# controller.net
KiCad netlist of a schematic drawn in EAGLE
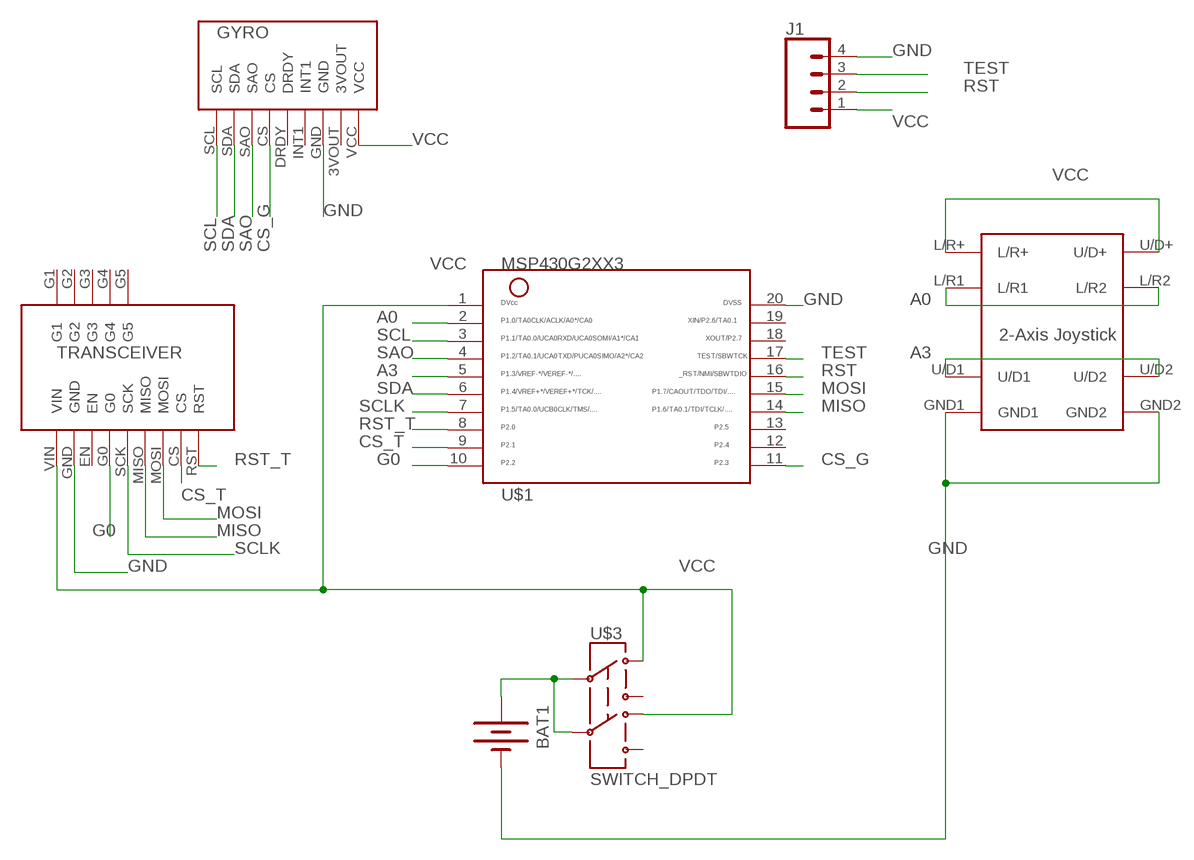
[diagram p0: schematic, sheet 1]

(export (version "E")
  (design (tool "Eeschema 10.0.6"))
  (components
    (comp (ref "BAT1")
      (value "BATTERY")
      (footprint "eagle-import:BATTERY_PACK_2AA")
      (libsource (lib "eagle-import") (part "BATTERY"))
    )
    (comp (ref "J1")
      (value "CONN_04LOCK")
      (footprint "eagle-import:1X04_LOCK")
      (libsource (lib "eagle-import") (part "CONN_04LOCK"))
    )
    (comp (ref "U$1")
      (value "MSP430G2XX3TSSOP")
      (footprint "eagle-import:PW20")
      (libsource (lib "eagle-import") (part "MSP430G2XX3TSSOP"))
    )
    (comp (ref "U$2")
      (value "PARALLAX-2AXIS-JOYSTICK")
      (footprint "eagle-import:PARALLAX-2AXIS-JOYSTICK")
      (libsource (lib "eagle-import") (part "PARALLAX-2AXIS-JOYSTICK"))
    )
    (comp (ref "U$3")
      (value "SWITCH_DPDT")
      (footprint "eagle-import:JS_DPDT_TH")
      (libsource (lib "eagle-import") (part "SWITCH_DPDT"))
    )
    (comp (ref "U$4")
      (value "ADAFRUIT-RFM69HCW-TRANSCEIVER")
      (footprint "eagle-import:ADAFRUIT-RFM69HCW-TRANSCEIVER")
      (libsource (lib "eagle-import") (part "ADAFRUIT-RFM69HCW-TRANSCEIVER"))
    )
    (comp (ref "U$5")
      (value "GYRO")
      (footprint "eagle-import:GYRO")
      (libsource (lib "eagle-import") (part "GYRO"))
    )
  )
  (nets
    (net (code "1") (name "/A0") (class "Default")
      (node (ref "U$1") (pin "2") (pinfunction "2_2") (pintype "bidirectional"))
      (node (ref "U$2") (pin "L/R1") (pinfunction "L/R1_L/R1") (pintype "bidirectional"))
      (node (ref "U$2") (pin "L/R2") (pinfunction "L/R2_L/R2") (pintype "bidirectional"))
    )
    (net (code "2") (name "/A3") (class "Default")
      (node (ref "U$1") (pin "5") (pinfunction "5_5") (pintype "bidirectional"))
      (node (ref "U$2") (pin "U/D1") (pinfunction "U/D1_U/D1") (pintype "bidirectional"))
      (node (ref "U$2") (pin "U/D2") (pinfunction "U/D2_U/D2") (pintype "bidirectional"))
    )
    (net (code "3") (name "/CS_G") (class "Default")
      (node (ref "U$1") (pin "11") (pinfunction "11_11") (pintype "bidirectional"))
      (node (ref "U$5") (pin "CS") (pinfunction "CS_CS") (pintype "bidirectional"))
    )
    (net (code "4") (name "/CS_T") (class "Default")
      (node (ref "U$1") (pin "9") (pinfunction "9_9") (pintype "bidirectional"))
      (node (ref "U$4") (pin "CS") (pinfunction "CS_CS") (pintype "bidirectional"))
    )
    (net (code "5") (name "/G0") (class "Default")
      (node (ref "U$1") (pin "10") (pinfunction "10_10") (pintype "bidirectional"))
      (node (ref "U$4") (pin "G0") (pinfunction "G0_G0") (pintype "bidirectional"))
    )
    (net (code "6") (name "/GND") (class "Default")
      (node (ref "BAT1") (pin "GND") (pinfunction "-_GND") (pintype "power_in"))
      (node (ref "J1") (pin "4") (pinfunction "4_4") (pintype "passive"))
      (node (ref "U$1") (pin "20") (pinfunction "20_20") (pintype "bidirectional"))
      (node (ref "U$2") (pin "GND1") (pinfunction "GND1_GND1") (pintype "bidirectional"))
      (node (ref "U$2") (pin "GND2") (pinfunction "GND2_GND2") (pintype "bidirectional"))
      (node (ref "U$4") (pin "GND") (pinfunction "GND_GND") (pintype "bidirectional"))
      (node (ref "U$5") (pin "GND") (pinfunction "GND_GND") (pintype "bidirectional"))
    )
    (net (code "7") (name "/MISO") (class "Default")
      (node (ref "U$1") (pin "14") (pinfunction "14_14") (pintype "bidirectional"))
      (node (ref "U$4") (pin "MISO") (pinfunction "MISO_MISO") (pintype "bidirectional"))
    )
    (net (code "8") (name "/MOSI") (class "Default")
      (node (ref "U$1") (pin "15") (pinfunction "15_15") (pintype "bidirectional"))
      (node (ref "U$4") (pin "MOSI") (pinfunction "MOSI_MOSI") (pintype "bidirectional"))
    )
    (net (code "9") (name "/RST") (class "Default")
      (node (ref "J1") (pin "2") (pinfunction "2_2") (pintype "passive"))
      (node (ref "U$1") (pin "16") (pinfunction "16_16") (pintype "bidirectional"))
    )
    (net (code "10") (name "/RST_T") (class "Default")
      (node (ref "U$1") (pin "8") (pinfunction "8_8") (pintype "bidirectional"))
      (node (ref "U$4") (pin "RST") (pinfunction "RST_RST") (pintype "bidirectional"))
    )
    (net (code "11") (name "/SAO") (class "Default")
      (node (ref "U$1") (pin "4") (pinfunction "4_4") (pintype "bidirectional"))
      (node (ref "U$5") (pin "SAO") (pinfunction "SAO_SAO") (pintype "bidirectional"))
    )
    (net (code "12") (name "/SCL") (class "Default")
      (node (ref "U$1") (pin "3") (pinfunction "3_3") (pintype "bidirectional"))
      (node (ref "U$5") (pin "SCL") (pinfunction "SCL_SCL") (pintype "bidirectional"))
    )
    (net (code "13") (name "/SCLK") (class "Default")
      (node (ref "U$1") (pin "7") (pinfunction "7_7") (pintype "bidirectional"))
      (node (ref "U$4") (pin "SCK") (pinfunction "SCK_SCK") (pintype "bidirectional"))
    )
    (net (code "14") (name "/SDA") (class "Default")
      (node (ref "U$1") (pin "6") (pinfunction "6_6") (pintype "bidirectional"))
      (node (ref "U$5") (pin "SDA") (pinfunction "SDA_SDA") (pintype "bidirectional"))
    )
    (net (code "15") (name "/TEST") (class "Default")
      (node (ref "J1") (pin "3") (pinfunction "3_3") (pintype "passive"))
      (node (ref "U$1") (pin "17") (pinfunction "17_17") (pintype "bidirectional"))
    )
    (net (code "16") (name "/VCC") (class "Default")
      (node (ref "J1") (pin "1") (pinfunction "1_1") (pintype "passive"))
      (node (ref "U$1") (pin "1") (pinfunction "1_1") (pintype "bidirectional"))
      (node (ref "U$2") (pin "L/R+") (pinfunction "L/R+_L/R+") (pintype "bidirectional"))
      (node (ref "U$2") (pin "U/D+") (pinfunction "U/D+_U/D+") (pintype "bidirectional"))
      (node (ref "U$3") (pin "1") (pinfunction "1_1") (pintype "bidirectional"))
      (node (ref "U$3") (pin "4") (pinfunction "4_4") (pintype "bidirectional"))
      (node (ref "U$4") (pin "VIN") (pinfunction "VIN_VIN") (pintype "bidirectional"))
      (node (ref "U$5") (pin "VCC") (pinfunction "VCC_VCC") (pintype "bidirectional"))
    )
    (net (code "17") (name "Net-(BAT1-+)") (class "Default")
      (node (ref "BAT1") (pin "3V") (pinfunction "+_3V") (pintype "power_in"))
      (node (ref "U$3") (pin "2") (pinfunction "2_2") (pintype "bidirectional"))
      (node (ref "U$3") (pin "5") (pinfunction "5_5") (pintype "bidirectional"))
    )
    (net (code "18") (name "unconnected-(U$1-Pad12)") (class "Default")
      (node (ref "U$1") (pin "12") (pinfunction "12_12") (pintype "bidirectional"))
    )
    (net (code "19") (name "unconnected-(U$1-Pad13)") (class "Default")
      (node (ref "U$1") (pin "13") (pinfunction "13_13") (pintype "bidirectional"))
    )
    (net (code "20") (name "unconnected-(U$1-Pad18)") (class "Default")
      (node (ref "U$1") (pin "18") (pinfunction "18_18") (pintype "bidirectional"))
    )
    (net (code "21") (name "unconnected-(U$1-Pad19)") (class "Default")
      (node (ref "U$1") (pin "19") (pinfunction "19_19") (pintype "bidirectional"))
    )
    (net (code "22") (name "unconnected-(U$3-Pad3)") (class "Default")
      (node (ref "U$3") (pin "3") (pinfunction "3_3") (pintype "bidirectional"))
    )
    (net (code "23") (name "unconnected-(U$3-Pad6)") (class "Default")
      (node (ref "U$3") (pin "6") (pinfunction "6_6") (pintype "bidirectional"))
    )
    (net (code "24") (name "unconnected-(U$4-PadEN)") (class "Default")
      (node (ref "U$4") (pin "EN") (pinfunction "EN_EN") (pintype "bidirectional"))
    )
    (net (code "25") (name "unconnected-(U$4-PadG1)") (class "Default")
      (node (ref "U$4") (pin "G1") (pinfunction "G1_G1") (pintype "bidirectional"))
    )
    (net (code "26") (name "unconnected-(U$4-PadG2)") (class "Default")
      (node (ref "U$4") (pin "G2") (pinfunction "G2_G2") (pintype "bidirectional"))
    )
    (net (code "27") (name "unconnected-(U$4-PadG3)") (class "Default")
      (node (ref "U$4") (pin "G3") (pinfunction "G3_G3") (pintype "bidirectional"))
    )
    (net (code "28") (name "unconnected-(U$4-PadG4)") (class "Default")
      (node (ref "U$4") (pin "G4") (pinfunction "G4_G4") (pintype "bidirectional"))
    )
    (net (code "29") (name "unconnected-(U$4-PadG5)") (class "Default")
      (node (ref "U$4") (pin "G5") (pinfunction "G5_G5") (pintype "bidirectional"))
    )
    (net (code "30") (name "unconnected-(U$5-Pad3VOUT)") (class "Default")
      (node (ref "U$5") (pin "3VOUT") (pinfunction "3VOUT_3VOUT") (pintype "bidirectional"))
    )
    (net (code "31") (name "unconnected-(U$5-PadDRDY)") (class "Default")
      (node (ref "U$5") (pin "DRDY") (pinfunction "DRDY_DRDY") (pintype "bidirectional"))
    )
    (net (code "32") (name "unconnected-(U$5-PadINT1)") (class "Default")
      (node (ref "U$5") (pin "INT1") (pinfunction "INT1_INT1") (pintype "bidirectional"))
    )
  )
)
